# Charger.net
KiCad netlist of a schematic drawn in Altium Designer
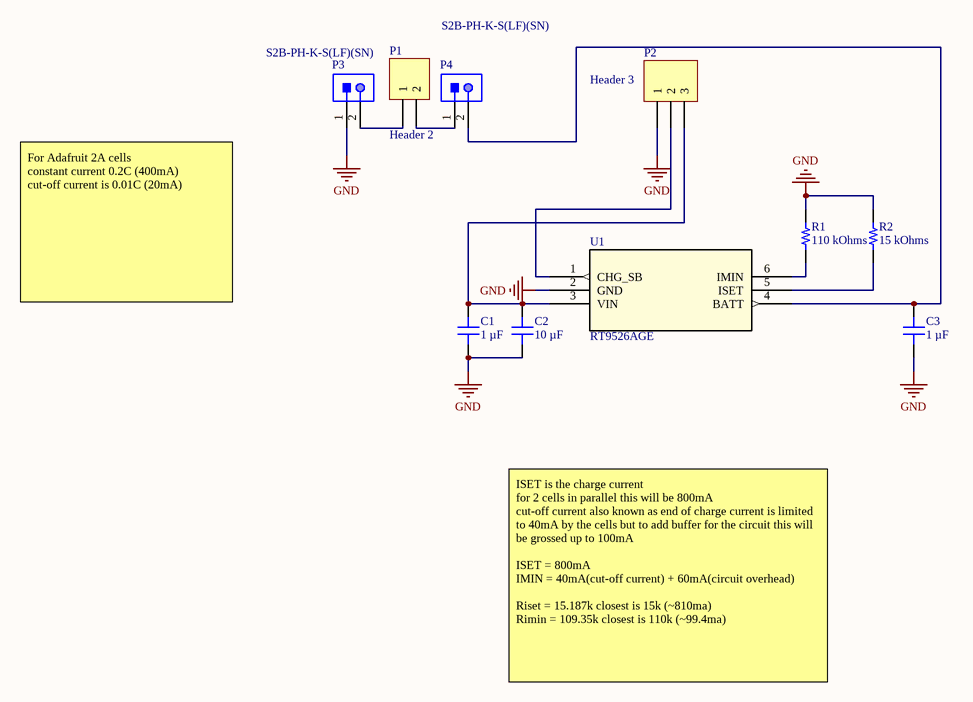
[diagram p0: Charger.SchDoc]

(export (version "E")
  (design (tool "Eeschema 10.0.6"))
  (components
    (comp (ref "C1")
      (value "1 µF")
      (footprint "CAP 0603_1608")
      (description "CAP CER 1UF 16V X7R 0603")
      (fields
        (field (name "PART NUMBER") "C1608X7R1C105K080AC")
        (field (name "MANUFACTURER") "TDK Corporation")
      )
      (libsource (lib "Celestial Altium Library - altium_library") (part "Capacitor"))
    )
    (comp (ref "C2")
      (value "10 µF")
      (footprint "CAP 0603_1608")
      (description "CAP CER 10UF 25V X5R 0603")
      (fields
        (field (name "PART NUMBER") "GRM188R61E106KA73J")
        (field (name "MANUFACTURER") "Murata Electronics")
      )
      (libsource (lib "Celestial Altium Library - altium_library") (part "Capacitor"))
    )
    (comp (ref "C3")
      (value "1 µF")
      (footprint "CAP 0603_1608")
      (description "CAP CER 1UF 16V X7R 0603")
      (fields
        (field (name "PART NUMBER") "C1608X7R1C105K080AC")
        (field (name "MANUFACTURER") "TDK Corporation")
      )
      (libsource (lib "Celestial Altium Library - altium_library") (part "Capacitor"))
    )
    (comp (ref "P1")
      (value "Header 2")
      (footprint "HDR1X2")
      (description "Header, 2-Pin")
      (fields (field (name "PUBLISHER") "Altium Limited"))
      (libsource (lib "Miscellaneous Connectors") (part "Header 2"))
    )
    (comp (ref "P2")
      (value "Header 3")
      (footprint "HDR1X3")
      (description "Header, 3-Pin")
      (fields (field (name "PUBLISHER") "Altium Limited"))
      (libsource (lib "Miscellaneous Connectors") (part "Header 3"))
    )
    (comp (ref "P3")
      (value "S2B-PH-K-S(LF)(SN)")
      (footprint "JST-S2B-PH-K-S_V")
      (fields (field (name "TOLERANCE") "20%"))
      (libsource (lib "Altium Content Vault") (part "CN-1P-M-R2"))
    )
    (comp (ref "P4")
      (value "S2B-PH-K-S(LF)(SN)")
      (footprint "JST-S2B-PH-K-S_V")
      (fields (field (name "TOLERANCE") "20%"))
      (libsource (lib "Altium Content Vault") (part "CN-1P-M-R2"))
    )
    (comp (ref "R1")
      (value "110 kOhms")
      (footprint "RES 0805_2012")
      (description "RES 110K OHM 1% 1/8W 0805")
      (fields (field (name "PART NUMBER") "RC0805FR-07110KL") (field (name "MANUFACTURER") "Yageo"))
      (libsource (lib "Celestial Altium Library - altium_library") (part "Resistor"))
    )
    (comp (ref "R2")
      (value "15 kOhms")
      (footprint "RES 0805_2012")
      (description "RES 15K OHM 1% 1/8W 0805")
      (fields (field (name "PART NUMBER") "RC0805FR-1315KL") (field (name "MANUFACTURER") "Yageo"))
      (libsource (lib "Celestial Altium Library - altium_library") (part "Resistor"))
    )
    (comp (ref "U1")
      (value "RT9526AGE")
      (footprint "SOT-23-6_RIT")
      (description "No Description Available")
      (fields (field (name "COPYRIGHT") "Copyright (C) 2023 Ultra Librarian. All rights reserved."))
      (libsource (lib "2020-09-26_17-27-19") (part "RT9526AGE"))
    )
  )
  (nets
    (net (code "1") (name "GND") (class "Default")
      (node (ref "C1") (pin "1") (pinfunction "1_1") (pintype "passive"))
      (node (ref "C2") (pin "1") (pinfunction "1_1") (pintype "passive"))
      (node (ref "C3") (pin "1") (pinfunction "1_1") (pintype "passive"))
      (node (ref "P2") (pin "1") (pinfunction "1_1") (pintype "passive"))
      (node (ref "P3") (pin "1") (pinfunction "1_1") (pintype "passive"))
      (node (ref "R1") (pin "2") (pinfunction "2_2") (pintype "passive"))
      (node (ref "R2") (pin "2") (pinfunction "2_2") (pintype "passive"))
      (node (ref "U1") (pin "2") (pinfunction "GND_2") (pintype "passive"))
    )
    (net (code "2") (name "Net-(P1-Pad1)") (class "Default")
      (node (ref "P1") (pin "1") (pinfunction "1_1") (pintype "passive"))
      (node (ref "P3") (pin "2") (pinfunction "2_2") (pintype "passive"))
    )
    (net (code "3") (name "Net-(P1-Pad2)") (class "Default")
      (node (ref "P1") (pin "2") (pinfunction "2_2") (pintype "passive"))
      (node (ref "P4") (pin "1") (pinfunction "1_1") (pintype "passive"))
    )
    (net (code "4") (name "Net-(U1-BATT)") (class "Default")
      (node (ref "C3") (pin "2") (pinfunction "2_2") (pintype "passive"))
      (node (ref "P4") (pin "2") (pinfunction "2_2") (pintype "passive"))
      (node (ref "U1") (pin "4") (pinfunction "BATT_4") (pintype "output"))
    )
    (net (code "5") (name "Net-(U1-CHG_SB)") (class "Default")
      (node (ref "P2") (pin "2") (pinfunction "2_2") (pintype "passive"))
      (node (ref "U1") (pin "1") (pinfunction "CHG_SB_1") (pintype "output"))
    )
    (net (code "6") (name "Net-(U1-IMIN)") (class "Default")
      (node (ref "R1") (pin "1") (pinfunction "1_1") (pintype "passive"))
      (node (ref "U1") (pin "6") (pinfunction "IMIN_6") (pintype "passive"))
    )
    (net (code "7") (name "Net-(U1-ISET)") (class "Default")
      (node (ref "R2") (pin "1") (pinfunction "1_1") (pintype "passive"))
      (node (ref "U1") (pin "5") (pinfunction "ISET_5") (pintype "passive"))
    )
    (net (code "8") (name "Net-(U1-VIN)") (class "Default")
      (node (ref "C1") (pin "2") (pinfunction "2_2") (pintype "passive"))
      (node (ref "C2") (pin "2") (pinfunction "2_2") (pintype "passive"))
      (node (ref "P2") (pin "3") (pinfunction "3_3") (pintype "passive"))
      (node (ref "U1") (pin "3") (pinfunction "VIN_3") (pintype "power_in"))
    )
  )
)
